# control2.net
KiCad netlist of a schematic drawn in Altium Designer
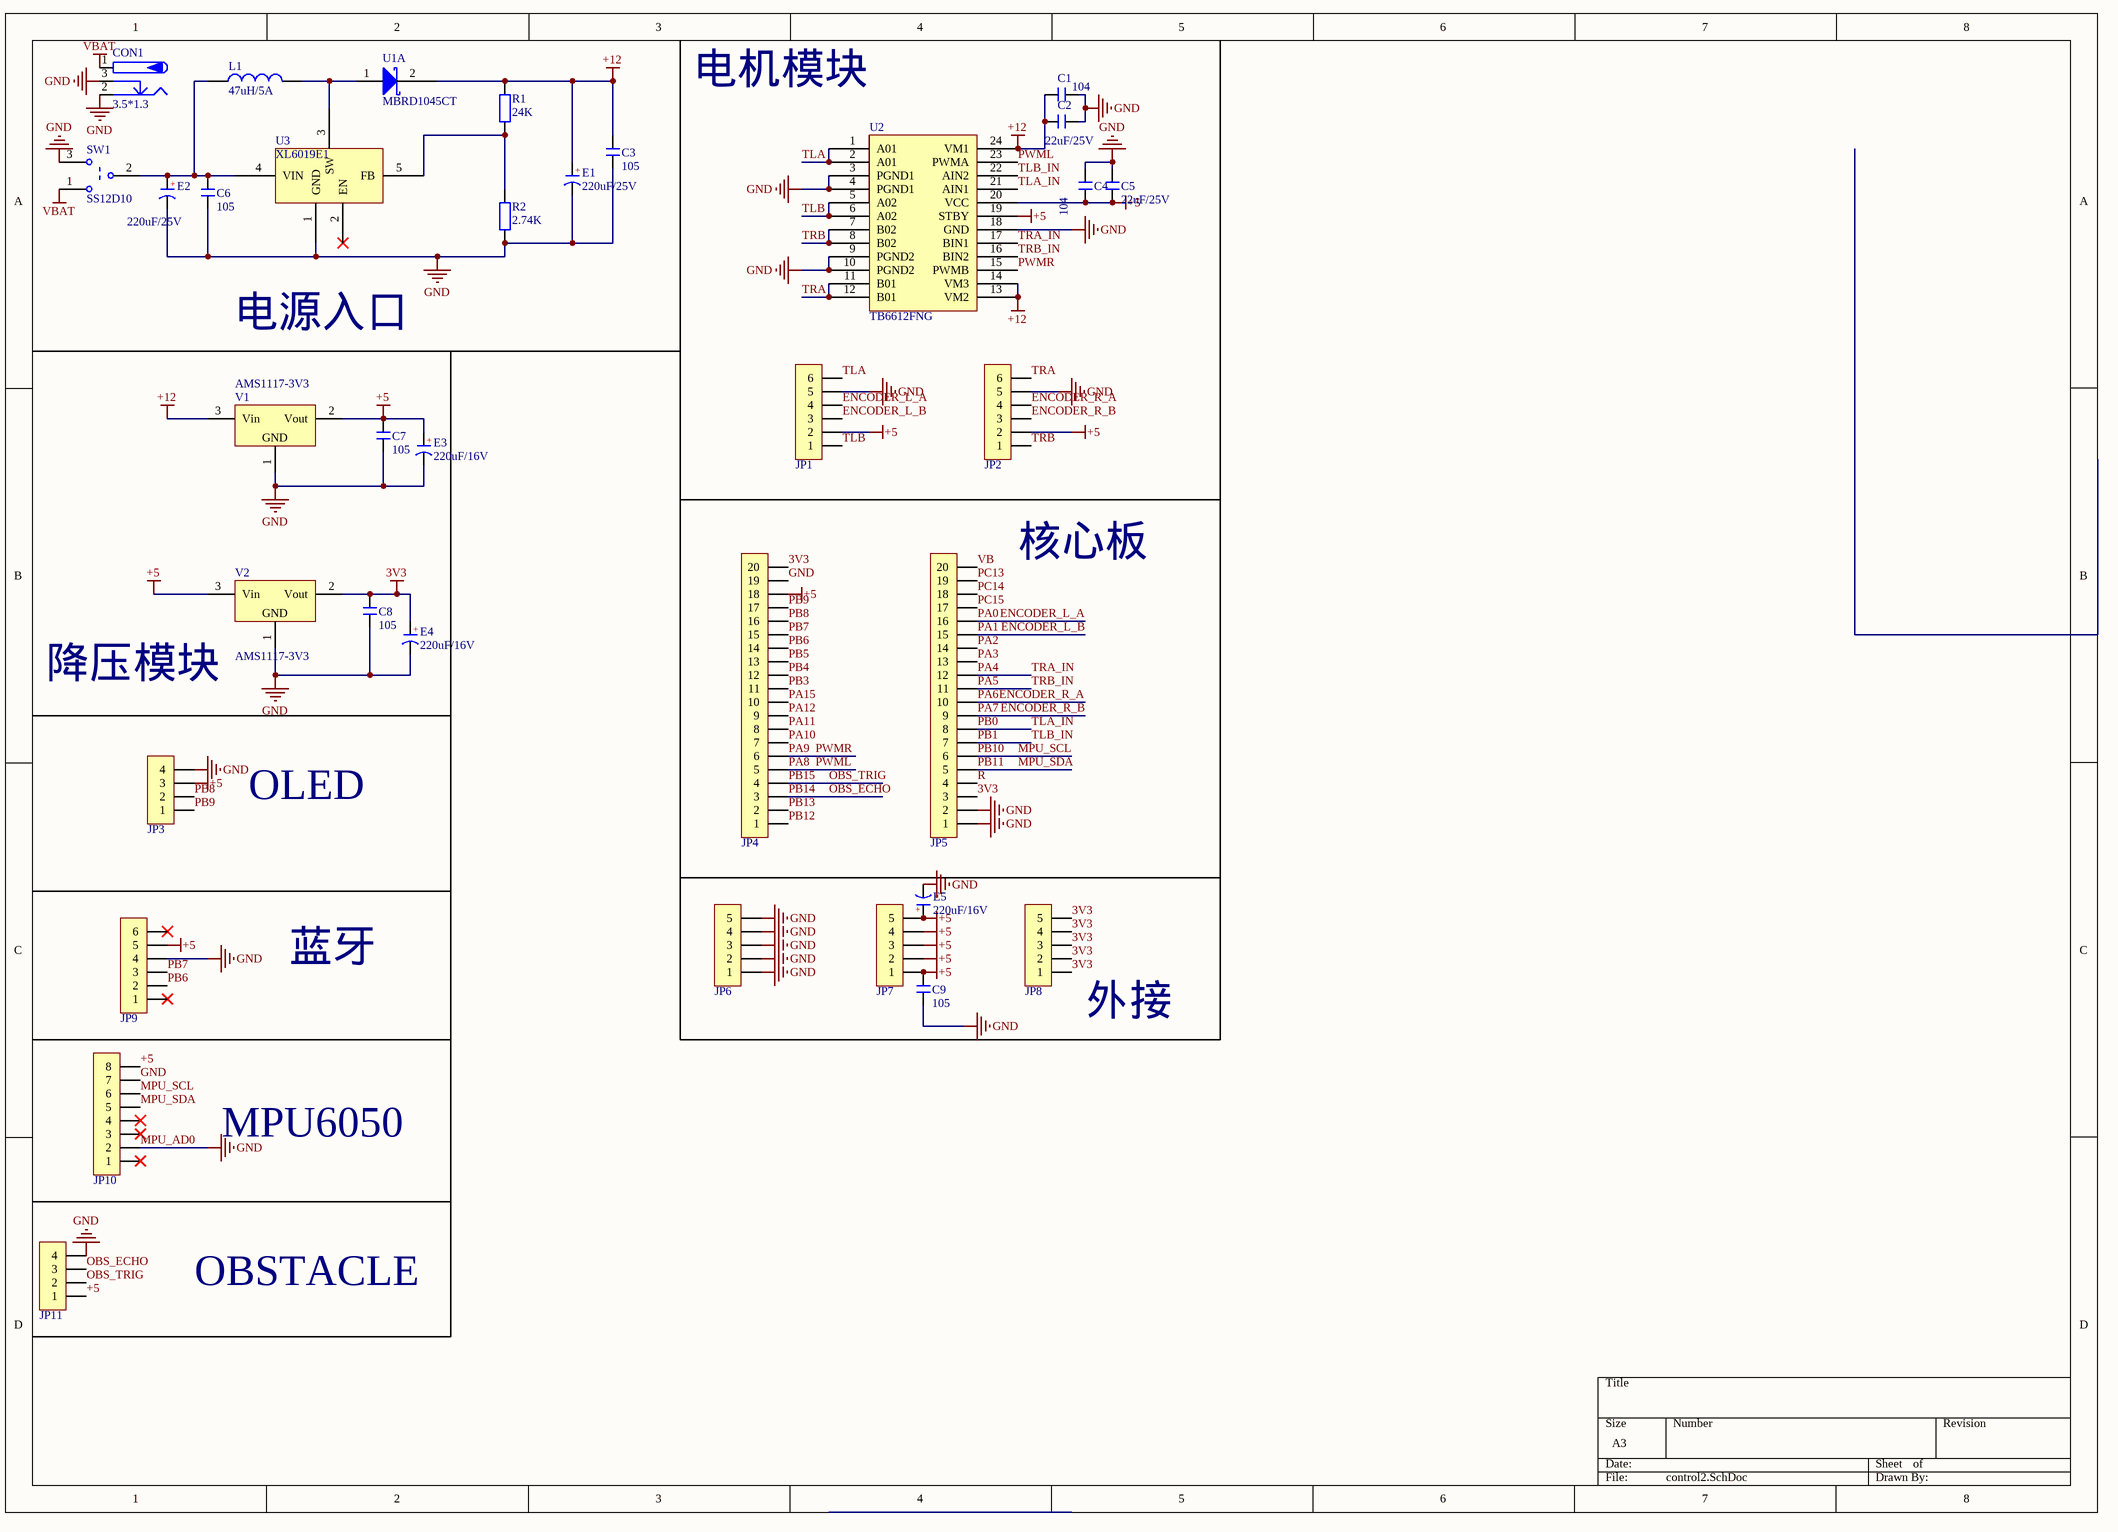
[diagram p0: control2.SchDoc]

(export (version "E")
  (design (tool "Eeschema 10.0.6"))
  (components
    (comp (ref "C1")
      (value "104")
      (footprint "C 0603_M")
      (description "贴片电容")
      (libsource (lib "0.1 - 电阻-电容-电感") (part "C"))
    )
    (comp (ref "C2")
      (value "22uF/25V")
      (footprint "C 0603_M")
      (description "贴片电容")
      (libsource (lib "0.1 - 电阻-电容-电感") (part "C"))
    )
    (comp (ref "C3")
      (value "105")
      (footprint "C 0603_M")
      (description "贴片电容")
      (libsource (lib "0.1 - 电阻-电容-电感") (part "C"))
    )
    (comp (ref "C4")
      (value "104")
      (footprint "C 0603_M")
      (description "贴片电容")
      (libsource (lib "0.1 - 电阻-电容-电感") (part "C"))
    )
    (comp (ref "C5")
      (value "22uF/25V")
      (footprint "C 0603_M")
      (description "贴片电容")
      (libsource (lib "0.1 - 电阻-电容-电感") (part "C"))
    )
    (comp (ref "C6")
      (value "105")
      (footprint "C 0603_M")
      (description "贴片电容")
      (libsource (lib "0.1 - 电阻-电容-电感") (part "C"))
    )
    (comp (ref "C7")
      (value "105")
      (footprint "C 0603_M")
      (description "贴片电容")
      (libsource (lib "0.1 - 电阻-电容-电感") (part "C"))
    )
    (comp (ref "C8")
      (value "105")
      (footprint "C 0603_M")
      (description "贴片电容")
      (libsource (lib "0.1 - 电阻-电容-电感") (part "C"))
    )
    (comp (ref "C9")
      (value "105")
      (footprint "C 0603_M")
      (description "贴片电容")
      (libsource (lib "0.1 - 电阻-电容-电感") (part "C"))
    )
    (comp (ref "CON1")
      (value "3.5*1.3")
      (footprint "DC-002")
      (description "低压电源接口")
      (fields (field (name "版权归属") "封装库来自淘宝 ID：黄晶宝石"))
      (libsource (lib "0.8 - 以太网-音频-USB插座") (part "P-DC"))
    )
    (comp (ref "E1")
      (value "220uF/25V")
      (footprint "CM E(8*10.2)")
      (description "贴片电解电容")
      (fields (field (name "版权归属") "封装库来自淘宝 ID：黄晶宝石"))
      (libsource (lib "0.1 - 电阻-电容-电感") (part "CE_SMD"))
    )
    (comp (ref "E2")
      (value "220uF/25V")
      (footprint "CM E(8*10.2)")
      (description "贴片电解电容")
      (fields (field (name "版权归属") "封装库来自淘宝 ID：黄晶宝石"))
      (libsource (lib "0.1 - 电阻-电容-电感") (part "CE_SMD"))
    )
    (comp (ref "E3")
      (value "220uF/16V")
      (footprint "CD A(3216)")
      (description "贴片钽电容")
      (libsource (lib "0.1 - 电阻-电容-电感") (part "CT"))
    )
    (comp (ref "E4")
      (value "220uF/16V")
      (footprint "CD A(3216)")
      (description "贴片钽电容")
      (libsource (lib "0.1 - 电阻-电容-电感") (part "CT"))
    )
    (comp (ref "E5")
      (value "220uF/16V")
      (footprint "CD A(3216)")
      (description "贴片钽电容")
      (libsource (lib "0.1 - 电阻-电容-电感") (part "CT"))
    )
    (comp (ref "JP1")
      (value "HDR-1X6")
      (footprint "XH2.54-LI-6P")
      (description "6P接插件")
      (fields (field (name "版权归属") "封装库来自淘宝 ID：黄晶宝石"))
      (libsource (lib "5.4 - 接插件-脚距2.54 (100mil) ") (part "Header 6"))
    )
    (comp (ref "JP2")
      (value "HDR-1X6")
      (footprint "XH2.54-LI-6P")
      (description "6P接插件")
      (fields (field (name "版权归属") "封装库来自淘宝 ID：黄晶宝石"))
      (libsource (lib "5.4 - 接插件-脚距2.54 (100mil) ") (part "Header 6"))
    )
    (comp (ref "JP3")
      (value "HDR-1X4")
      (footprint "HDR2.54-M-LI-4P")
      (description "4P接插件")
      (fields (field (name "版权归属") "封装库来自淘宝 ID：黄晶宝石"))
      (libsource (lib "5.4 - 接插件-脚距2.54 (100mil) ") (part "Header 4"))
    )
    (comp (ref "JP4")
      (value "HDR-1X20")
      (footprint "HDR2.54-M-LI-20P")
      (description "20P接插件")
      (fields (field (name "版权归属") "封装库来自淘宝 ID：黄晶宝石"))
      (libsource (lib "5.4 - 接插件-脚距2.54 (100mil) ") (part "Header 20"))
    )
    (comp (ref "JP5")
      (value "HDR-1X20")
      (footprint "HDR2.54-M-LI-20P")
      (description "20P接插件")
      (fields (field (name "版权归属") "封装库来自淘宝 ID：黄晶宝石"))
      (libsource (lib "5.4 - 接插件-脚距2.54 (100mil) ") (part "Header 20"))
    )
    (comp (ref "JP6")
      (value "HDR-1X5")
      (footprint "HDR2.54-LI-5P")
      (description "5P接插件")
      (fields (field (name "版权归属") "封装库来自淘宝 ID：黄晶宝石"))
      (libsource (lib "5.4 - 接插件-脚距2.54 (100mil) ") (part "Header 5"))
    )
    (comp (ref "JP7")
      (value "HDR-1X5")
      (footprint "HDR2.54-LI-5P")
      (description "5P接插件")
      (fields (field (name "版权归属") "封装库来自淘宝 ID：黄晶宝石"))
      (libsource (lib "5.4 - 接插件-脚距2.54 (100mil) ") (part "Header 5"))
    )
    (comp (ref "JP8")
      (value "HDR-1X5")
      (footprint "HDR2.54-LI-5P")
      (description "5P接插件")
      (fields (field (name "版权归属") "封装库来自淘宝 ID：黄晶宝石"))
      (libsource (lib "5.4 - 接插件-脚距2.54 (100mil) ") (part "Header 5"))
    )
    (comp (ref "JP9")
      (value "HDR-1X6")
      (footprint "HDR2.54-M-LI-6P")
      (description "6P接插件")
      (fields (field (name "版权归属") "封装库来自淘宝 ID：黄晶宝石"))
      (libsource (lib "5.4 - 接插件-脚距2.54 (100mil) ") (part "Header 6"))
    )
    (comp (ref "JP10")
      (value "HDR-1X8")
      (footprint "HDR2.54-M-LI-8P")
      (description "8P接插件")
      (fields (field (name "版权归属") "封装库来自淘宝 ID：黄晶宝石"))
      (libsource (lib "5.4 - 接插件-脚距2.54 (100mil) ") (part "Header 8"))
    )
    (comp (ref "JP11")
      (value "HDR-1X4")
      (footprint "HDR2.54-M-LI-4P")
      (description "4P接插件")
      (fields (field (name "版权归属") "封装库来自淘宝 ID：黄晶宝石"))
      (libsource (lib "5.4 - 接插件-脚距2.54 (100mil) ") (part "Header 4"))
    )
    (comp (ref "L1")
      (value "47uH/5A")
      (footprint "L 1206")
      (description "小功率贴片电感")
      (libsource (lib "0.1 - 电阻-电容-电感") (part "L"))
    )
    (comp (ref "R1")
      (value "24K")
      (footprint "R 0603_M")
      (description "贴片电阻")
      (fields (field (name "版权归属") "来自淘宝 ID：黄晶宝石"))
      (libsource (lib "0.1 - 电阻-电容-电感") (part "R"))
    )
    (comp (ref "R2")
      (value "2.74K")
      (footprint "R 0603_M")
      (description "贴片电阻")
      (fields (field (name "版权归属") "来自淘宝 ID：黄晶宝石"))
      (libsource (lib "0.1 - 电阻-电容-电感") (part "R"))
    )
    (comp (ref "SW1") (value "SS12D10") (footprint "SS12D10") (libsource (lib "LJY_LIB") (part "SS12D10")))
    (comp (ref "U1")
      (value "MBRD1045CT")
      (footprint "TO-252-3_L6.5-W5.5-P4.6-LS9.5-BL")
      (libsource (lib "LJY_LIB") (part "MBRD1045CT"))
    )
    (comp (ref "U2")
      (value "TB6612FNG")
      (footprint "TSOP65P760X160-24N")
      (libsource (lib "LJY_LIB") (part "TB6612FNG"))
    )
    (comp (ref "U3") (value "XL6019E1") (footprint "TO-263-5") (libsource (lib "LJY_LIB") (part "XL6019E1")))
    (comp (ref "V1")
      (value "AMS1117-3V3")
      (footprint "SOT223_L")
      (description "三端稳压芯片")
      (libsource (lib "1.1 - 电源类芯片") (part "AMS1117"))
    )
    (comp (ref "V2")
      (value "AMS1117-3V3")
      (footprint "SOT223_L")
      (description "三端稳压芯片")
      (libsource (lib "1.1 - 电源类芯片") (part "AMS1117"))
    )
  )
  (nets
    (net (code "1") (name "+5") (class "Default")
      (node (ref "C4") (pin "2") (pinfunction "2_2") (pintype "passive"))
      (node (ref "C5") (pin "2") (pinfunction "2_2") (pintype "passive"))
      (node (ref "C7") (pin "2") (pinfunction "2_2") (pintype "passive"))
      (node (ref "C9") (pin "2") (pinfunction "2_2") (pintype "passive"))
      (node (ref "E3") (pin "1") (pinfunction "A_1") (pintype "passive"))
      (node (ref "E5") (pin "1") (pinfunction "A_1") (pintype "passive"))
      (node (ref "JP1") (pin "2") (pinfunction "2_2") (pintype "passive"))
      (node (ref "JP10") (pin "8") (pinfunction "8_8") (pintype "passive"))
      (node (ref "JP11") (pin "1") (pinfunction "1_1") (pintype "passive"))
      (node (ref "JP2") (pin "2") (pinfunction "2_2") (pintype "passive"))
      (node (ref "JP3") (pin "3") (pinfunction "3_3") (pintype "passive"))
      (node (ref "JP4") (pin "18") (pinfunction "18_18") (pintype "passive"))
      (node (ref "JP7") (pin "1") (pinfunction "1_1") (pintype "passive"))
      (node (ref "JP7") (pin "2") (pinfunction "2_2") (pintype "passive"))
      (node (ref "JP7") (pin "3") (pinfunction "3_3") (pintype "passive"))
      (node (ref "JP7") (pin "4") (pinfunction "4_4") (pintype "passive"))
      (node (ref "JP7") (pin "5") (pinfunction "5_5") (pintype "passive"))
      (node (ref "JP9") (pin "5") (pinfunction "5_5") (pintype "passive"))
      (node (ref "U2") (pin "19") (pinfunction "STBY_19") (pintype "passive"))
      (node (ref "U2") (pin "20") (pinfunction "VCC_20") (pintype "passive"))
      (node (ref "V1") (pin "2") (pinfunction "Vout_2") (pintype "passive"))
      (node (ref "V2") (pin "3") (pinfunction "Vin_3") (pintype "passive"))
    )
    (net (code "2") (name "+12") (class "Default")
      (node (ref "C1") (pin "2") (pinfunction "2_2") (pintype "passive"))
      (node (ref "C2") (pin "2") (pinfunction "2_2") (pintype "passive"))
      (node (ref "C3") (pin "2") (pinfunction "2_2") (pintype "passive"))
      (node (ref "E1") (pin "1") (pinfunction "A_1") (pintype "passive"))
      (node (ref "R1") (pin "2") (pinfunction "2_2") (pintype "passive"))
      (node (ref "U1") (pin "2") (pinfunction "3_2") (pintype "passive"))
      (node (ref "U2") (pin "13") (pinfunction "VM2_13") (pintype "passive"))
      (node (ref "U2") (pin "14") (pinfunction "VM3_14") (pintype "passive"))
      (node (ref "U2") (pin "24") (pinfunction "VM1_24") (pintype "passive"))
      (node (ref "V1") (pin "3") (pinfunction "Vin_3") (pintype "passive"))
    )
    (net (code "3") (name "/ENCODER_L_A") (class "Default")
      (node (ref "JP1") (pin "4") (pinfunction "4_4") (pintype "passive"))
      (node (ref "JP5") (pin "16") (pinfunction "16_16") (pintype "passive"))
    )
    (net (code "4") (name "/ENCODER_L_B") (class "Default")
      (node (ref "JP1") (pin "3") (pinfunction "3_3") (pintype "passive"))
      (node (ref "JP5") (pin "15") (pinfunction "15_15") (pintype "passive"))
    )
    (net (code "5") (name "/ENCODER_R_A") (class "Default")
      (node (ref "JP2") (pin "4") (pinfunction "4_4") (pintype "passive"))
      (node (ref "JP5") (pin "10") (pinfunction "10_10") (pintype "passive"))
    )
    (net (code "6") (name "/ENCODER_R_B") (class "Default")
      (node (ref "JP2") (pin "3") (pinfunction "3_3") (pintype "passive"))
      (node (ref "JP5") (pin "9") (pinfunction "9_9") (pintype "passive"))
    )
    (net (code "7") (name "/MPU_SCL") (class "Default")
      (node (ref "JP10") (pin "6") (pinfunction "6_6") (pintype "passive"))
      (node (ref "JP5") (pin "6") (pinfunction "6_6") (pintype "passive"))
    )
    (net (code "8") (name "/MPU_SDA") (class "Default")
      (node (ref "JP10") (pin "5") (pinfunction "5_5") (pintype "passive"))
      (node (ref "JP5") (pin "5") (pinfunction "5_5") (pintype "passive"))
    )
    (net (code "9") (name "/OBS_ECHO") (class "Default")
      (node (ref "JP11") (pin "3") (pinfunction "3_3") (pintype "passive"))
      (node (ref "JP4") (pin "3") (pinfunction "3_3") (pintype "passive"))
    )
    (net (code "10") (name "/OBS_TRIG") (class "Default")
      (node (ref "JP11") (pin "2") (pinfunction "2_2") (pintype "passive"))
      (node (ref "JP4") (pin "4") (pinfunction "4_4") (pintype "passive"))
    )
    (net (code "11") (name "/PA2") (class "Default")
      (node (ref "JP5") (pin "14") (pinfunction "14_14") (pintype "passive"))
    )
    (net (code "12") (name "/PA3") (class "Default")
      (node (ref "JP5") (pin "13") (pinfunction "13_13") (pintype "passive"))
    )
    (net (code "13") (name "/PA4") (class "Default")
      (node (ref "JP5") (pin "12") (pinfunction "12_12") (pintype "passive"))
      (node (ref "U2") (pin "17") (pinfunction "BIN1_17") (pintype "passive"))
    )
    (net (code "14") (name "/PA5") (class "Default")
      (node (ref "JP5") (pin "11") (pinfunction "11_11") (pintype "passive"))
      (node (ref "U2") (pin "16") (pinfunction "BIN2_16") (pintype "passive"))
    )
    (net (code "15") (name "/PA8") (class "Default")
      (node (ref "JP4") (pin "5") (pinfunction "5_5") (pintype "passive"))
      (node (ref "U2") (pin "23") (pinfunction "PWMA_23") (pintype "passive"))
    )
    (net (code "16") (name "/PA9") (class "Default")
      (node (ref "JP4") (pin "6") (pinfunction "6_6") (pintype "passive"))
      (node (ref "U2") (pin "15") (pinfunction "PWMB_15") (pintype "passive"))
    )
    (net (code "17") (name "/PA10") (class "Default")
      (node (ref "JP4") (pin "7") (pinfunction "7_7") (pintype "passive"))
    )
    (net (code "18") (name "/PA11") (class "Default")
      (node (ref "JP4") (pin "8") (pinfunction "8_8") (pintype "passive"))
    )
    (net (code "19") (name "/PA12") (class "Default")
      (node (ref "JP4") (pin "9") (pinfunction "9_9") (pintype "passive"))
    )
    (net (code "20") (name "/PA15") (class "Default")
      (node (ref "JP4") (pin "10") (pinfunction "10_10") (pintype "passive"))
    )
    (net (code "21") (name "/PB0") (class "Default")
      (node (ref "JP5") (pin "8") (pinfunction "8_8") (pintype "passive"))
      (node (ref "U2") (pin "21") (pinfunction "AIN1_21") (pintype "passive"))
    )
    (net (code "22") (name "/PB1") (class "Default")
      (node (ref "JP5") (pin "7") (pinfunction "7_7") (pintype "passive"))
      (node (ref "U2") (pin "22") (pinfunction "AIN2_22") (pintype "passive"))
    )
    (net (code "23") (name "/PB3") (class "Default")
      (node (ref "JP4") (pin "11") (pinfunction "11_11") (pintype "passive"))
    )
    (net (code "24") (name "/PB4") (class "Default")
      (node (ref "JP4") (pin "12") (pinfunction "12_12") (pintype "passive"))
    )
    (net (code "25") (name "/PB5") (class "Default")
      (node (ref "JP4") (pin "13") (pinfunction "13_13") (pintype "passive"))
    )
    (net (code "26") (name "/PB6") (class "Default")
      (node (ref "JP4") (pin "14") (pinfunction "14_14") (pintype "passive"))
      (node (ref "JP9") (pin "2") (pinfunction "2_2") (pintype "passive"))
    )
    (net (code "27") (name "/PB7") (class "Default")
      (node (ref "JP4") (pin "15") (pinfunction "15_15") (pintype "passive"))
      (node (ref "JP9") (pin "3") (pinfunction "3_3") (pintype "passive"))
    )
    (net (code "28") (name "/PB8") (class "Default")
      (node (ref "JP3") (pin "2") (pinfunction "2_2") (pintype "passive"))
      (node (ref "JP4") (pin "16") (pinfunction "16_16") (pintype "passive"))
    )
    (net (code "29") (name "/PB9") (class "Default")
      (node (ref "JP3") (pin "1") (pinfunction "1_1") (pintype "passive"))
      (node (ref "JP4") (pin "17") (pinfunction "17_17") (pintype "passive"))
    )
    (net (code "30") (name "/PB12") (class "Default")
      (node (ref "JP4") (pin "1") (pinfunction "1_1") (pintype "passive"))
    )
    (net (code "31") (name "/PB13") (class "Default")
      (node (ref "JP4") (pin "2") (pinfunction "2_2") (pintype "passive"))
    )
    (net (code "32") (name "/PC13") (class "Default")
      (node (ref "JP5") (pin "19") (pinfunction "19_19") (pintype "passive"))
    )
    (net (code "33") (name "/PC14") (class "Default")
      (node (ref "JP5") (pin "18") (pinfunction "18_18") (pintype "passive"))
    )
    (net (code "34") (name "/PC15") (class "Default")
      (node (ref "JP5") (pin "17") (pinfunction "17_17") (pintype "passive"))
    )
    (net (code "35") (name "/R") (class "Default")
      (node (ref "JP5") (pin "4") (pinfunction "4_4") (pintype "passive"))
    )
    (net (code "36") (name "/TLA") (class "Default")
      (node (ref "JP1") (pin "6") (pinfunction "6_6") (pintype "passive"))
      (node (ref "U2") (pin "1") (pinfunction "A01_1") (pintype "passive"))
      (node (ref "U2") (pin "2") (pinfunction "A01_2") (pintype "passive"))
    )
    (net (code "37") (name "/TLB") (class "Default")
      (node (ref "JP1") (pin "1") (pinfunction "1_1") (pintype "passive"))
      (node (ref "U2") (pin "5") (pinfunction "A02_5") (pintype "passive"))
      (node (ref "U2") (pin "6") (pinfunction "A02_6") (pintype "passive"))
    )
    (net (code "38") (name "/TRA") (class "Default")
      (node (ref "JP2") (pin "6") (pinfunction "6_6") (pintype "passive"))
      (node (ref "U2") (pin "11") (pinfunction "B01_11") (pintype "passive"))
      (node (ref "U2") (pin "12") (pinfunction "B01_12") (pintype "passive"))
    )
    (net (code "39") (name "/TRB") (class "Default")
      (node (ref "JP2") (pin "1") (pinfunction "1_1") (pintype "passive"))
      (node (ref "U2") (pin "7") (pinfunction "B02_7") (pintype "passive"))
      (node (ref "U2") (pin "8") (pinfunction "B02_8") (pintype "passive"))
    )
    (net (code "40") (name "/VB") (class "Default")
      (node (ref "JP5") (pin "20") (pinfunction "20_20") (pintype "passive"))
    )
    (net (code "41") (name "3V3") (class "Default")
      (node (ref "C8") (pin "2") (pinfunction "2_2") (pintype "passive"))
      (node (ref "E4") (pin "1") (pinfunction "A_1") (pintype "passive"))
      (node (ref "JP4") (pin "20") (pinfunction "20_20") (pintype "passive"))
      (node (ref "JP5") (pin "3") (pinfunction "3_3") (pintype "passive"))
      (node (ref "JP8") (pin "1") (pinfunction "1_1") (pintype "passive"))
      (node (ref "JP8") (pin "2") (pinfunction "2_2") (pintype "passive"))
      (node (ref "JP8") (pin "3") (pinfunction "3_3") (pintype "passive"))
      (node (ref "JP8") (pin "4") (pinfunction "4_4") (pintype "passive"))
      (node (ref "JP8") (pin "5") (pinfunction "5_5") (pintype "passive"))
      (node (ref "V2") (pin "2") (pinfunction "Vout_2") (pintype "passive"))
    )
    (net (code "42") (name "GND") (class "Default")
      (node (ref "C1") (pin "1") (pinfunction "1_1") (pintype "passive"))
      (node (ref "C2") (pin "1") (pinfunction "1_1") (pintype "passive"))
      (node (ref "C3") (pin "1") (pinfunction "1_1") (pintype "passive"))
      (node (ref "C4") (pin "1") (pinfunction "1_1") (pintype "passive"))
      (node (ref "C5") (pin "1") (pinfunction "1_1") (pintype "passive"))
      (node (ref "C6") (pin "1") (pinfunction "1_1") (pintype "passive"))
      (node (ref "C7") (pin "1") (pinfunction "1_1") (pintype "passive"))
      (node (ref "C8") (pin "1") (pinfunction "1_1") (pintype "passive"))
      (node (ref "C9") (pin "1") (pinfunction "1_1") (pintype "passive"))
      (node (ref "CON1") (pin "2") (pintype "power_in"))
      (node (ref "CON1") (pin "3") (pintype "power_in"))
      (node (ref "E1") (pin "2") (pinfunction "K_2") (pintype "passive"))
      (node (ref "E2") (pin "2") (pinfunction "K_2") (pintype "passive"))
      (node (ref "E3") (pin "2") (pinfunction "K_2") (pintype "passive"))
      (node (ref "E4") (pin "2") (pinfunction "K_2") (pintype "passive"))
      (node (ref "E5") (pin "2") (pinfunction "K_2") (pintype "passive"))
      (node (ref "JP1") (pin "5") (pinfunction "5_5") (pintype "passive"))
      (node (ref "JP10") (pin "2") (pinfunction "2_2") (pintype "passive"))
      (node (ref "JP10") (pin "7") (pinfunction "7_7") (pintype "passive"))
      (node (ref "JP11") (pin "4") (pinfunction "4_4") (pintype "passive"))
      (node (ref "JP2") (pin "5") (pinfunction "5_5") (pintype "passive"))
      (node (ref "JP3") (pin "4") (pinfunction "4_4") (pintype "passive"))
      (node (ref "JP4") (pin "19") (pinfunction "19_19") (pintype "passive"))
      (node (ref "JP5") (pin "1") (pinfunction "1_1") (pintype "passive"))
      (node (ref "JP5") (pin "2") (pinfunction "2_2") (pintype "passive"))
      (node (ref "JP6") (pin "1") (pinfunction "1_1") (pintype "passive"))
      (node (ref "JP6") (pin "2") (pinfunction "2_2") (pintype "passive"))
      (node (ref "JP6") (pin "3") (pinfunction "3_3") (pintype "passive"))
      (node (ref "JP6") (pin "4") (pinfunction "4_4") (pintype "passive"))
      (node (ref "JP6") (pin "5") (pinfunction "5_5") (pintype "passive"))
      (node (ref "JP9") (pin "4") (pinfunction "4_4") (pintype "passive"))
      (node (ref "R2") (pin "2") (pinfunction "2_2") (pintype "passive"))
      (node (ref "SW1") (pin "3") (pinfunction "NO1_3") (pintype "passive"))
      (node (ref "U2") (pin "10") (pinfunction "PGND2_10") (pintype "passive"))
      (node (ref "U2") (pin "18") (pinfunction "GND_18") (pintype "passive"))
      (node (ref "U2") (pin "3") (pinfunction "PGND1_3") (pintype "passive"))
      (node (ref "U2") (pin "4") (pinfunction "PGND1_4") (pintype "passive"))
      (node (ref "U2") (pin "9") (pinfunction "PGND2_9") (pintype "passive"))
      (node (ref "U3") (pin "1") (pinfunction "GND_1") (pintype "passive"))
      (node (ref "V1") (pin "1") (pinfunction "GND_1") (pintype "passive"))
      (node (ref "V2") (pin "1") (pinfunction "GND_1") (pintype "passive"))
    )
    (net (code "43") (name "Net-(E2-A)") (class "Default")
      (node (ref "C6") (pin "2") (pinfunction "2_2") (pintype "passive"))
      (node (ref "E2") (pin "1") (pinfunction "A_1") (pintype "passive"))
      (node (ref "L1") (pin "1") (pinfunction "1_1") (pintype "passive"))
      (node (ref "SW1") (pin "2") (pinfunction "COM2_2") (pintype "passive"))
      (node (ref "U3") (pin "4") (pinfunction "VIN_4") (pintype "passive"))
    )
    (net (code "44") (name "Net-(U1A-A)") (class "Default")
      (node (ref "L1") (pin "2") (pinfunction "2_2") (pintype "passive"))
      (node (ref "U1") (pin "1") (pinfunction "A_1") (pintype "passive"))
      (node (ref "U3") (pin "3") (pinfunction "SW_3") (pintype "passive"))
    )
    (net (code "45") (name "Net-(U3-FB)") (class "Default")
      (node (ref "R1") (pin "1") (pinfunction "1_1") (pintype "passive"))
      (node (ref "R2") (pin "1") (pinfunction "1_1") (pintype "passive"))
      (node (ref "U3") (pin "5") (pinfunction "FB_5") (pintype "passive"))
    )
    (net (code "46") (name "VBAT") (class "Default")
      (node (ref "CON1") (pin "1") (pintype "power_in"))
      (node (ref "SW1") (pin "1") (pinfunction "NC1_1") (pintype "passive"))
    )
    (net (code "47") (name "unconnected-(JP9-Pad1)") (class "Default")
      (node (ref "JP9") (pin "1") (pinfunction "1_1") (pintype "passive+no_connect"))
    )
    (net (code "48") (name "unconnected-(JP9-Pad6)") (class "Default")
      (node (ref "JP9") (pin "6") (pinfunction "6_6") (pintype "passive+no_connect"))
    )
    (net (code "49") (name "unconnected-(JP10-Pad1)") (class "Default")
      (node (ref "JP10") (pin "1") (pinfunction "1_1") (pintype "passive+no_connect"))
    )
    (net (code "50") (name "unconnected-(JP10-Pad3)") (class "Default")
      (node (ref "JP10") (pin "3") (pinfunction "3_3") (pintype "passive+no_connect"))
    )
    (net (code "51") (name "unconnected-(JP10-Pad4)") (class "Default")
      (node (ref "JP10") (pin "4") (pinfunction "4_4") (pintype "passive+no_connect"))
    )
    (net (code "52") (name "unconnected-(U3-EN-Pad2)") (class "Default")
      (node (ref "U3") (pin "2") (pinfunction "EN_2") (pintype "passive+no_connect"))
    )
  )
)
